# Nuio_Left_Keyboard_Rev_G_Power.net
KiCad netlist of a schematic drawn in Altium Designer
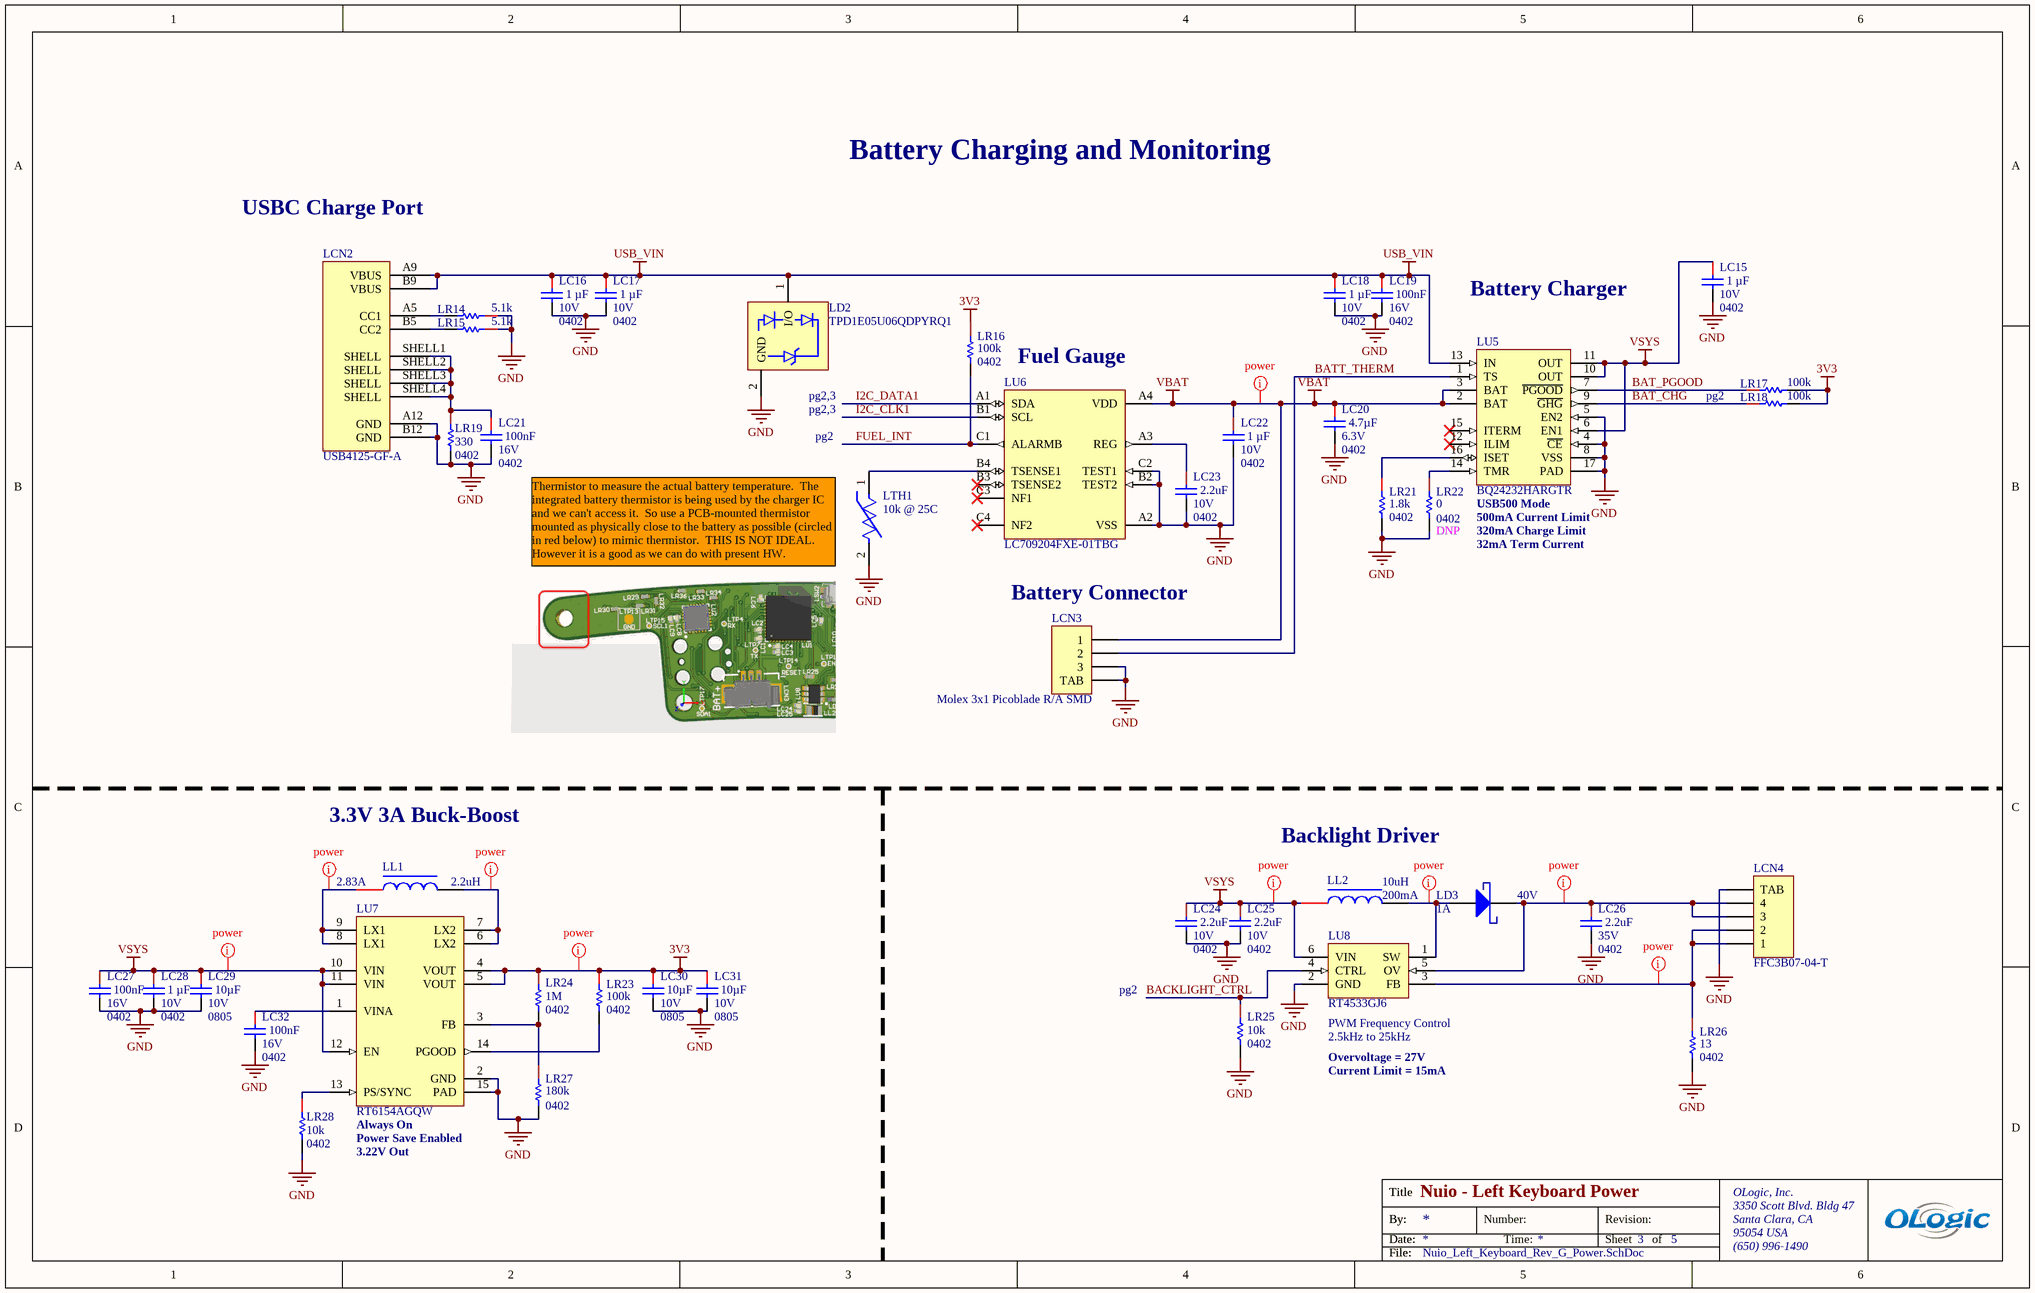
[diagram p0: Nuio_Left_Keyboard_Rev_G_Power.SchDoc]

(export (version "E")
  (design (tool "Eeschema 10.0.6"))
  (components
    (comp (ref "LC15")
      (value "CAP CER 1UF 10V X5R 0402")
      (footprint "CAPC0402(1005)_L")
      (description "±20% 10V Ceramic Capacitor X5R 0402 (1005 Metric)")
      (fields
        (field (name "PACKAGE (IMPERIAL)") "0402")
        (field (name "VOLTAGE (RATED)") "10V")
        (field (name "CAPACITANCE") "1 µF")
        (field (name "MANUFACTURER PART NUMBER") "CC0402MRX5R6BB105")
        (field (name "TOLERANCE") "±20%")
      )
      (libsource (lib "OLogic Nexus Vault") (part "OL_Capacitor"))
    )
    (comp (ref "LC16")
      (value "CAP CER 1UF 10V X5R 0402")
      (footprint "CAPC0402(1005)_L")
      (description "±20% 10V Ceramic Capacitor X5R 0402 (1005 Metric)")
      (fields
        (field (name "PACKAGE (IMPERIAL)") "0402")
        (field (name "VOLTAGE (RATED)") "10V")
        (field (name "CAPACITANCE") "1 µF")
        (field (name "MANUFACTURER PART NUMBER") "CC0402MRX5R6BB105")
        (field (name "TOLERANCE") "±20%")
      )
      (libsource (lib "OLogic Nexus Vault") (part "OL_Capacitor"))
    )
    (comp (ref "LC17")
      (value "CAP CER 1UF 10V X5R 0402")
      (footprint "CAPC0402(1005)_L")
      (description "±20% 10V Ceramic Capacitor X5R 0402 (1005 Metric)")
      (fields
        (field (name "PACKAGE (IMPERIAL)") "0402")
        (field (name "VOLTAGE (RATED)") "10V")
        (field (name "CAPACITANCE") "1 µF")
        (field (name "MANUFACTURER PART NUMBER") "CC0402MRX5R6BB105")
        (field (name "TOLERANCE") "±20%")
      )
      (libsource (lib "OLogic Nexus Vault") (part "OL_Capacitor"))
    )
    (comp (ref "LC18")
      (value "CAP CER 1UF 10V X5R 0402")
      (footprint "CAPC0402(1005)_L")
      (description "±20% 10V Ceramic Capacitor X5R 0402 (1005 Metric)")
      (fields
        (field (name "PACKAGE (IMPERIAL)") "0402")
        (field (name "VOLTAGE (RATED)") "10V")
        (field (name "CAPACITANCE") "1 µF")
        (field (name "MANUFACTURER PART NUMBER") "CC0402MRX5R6BB105")
        (field (name "TOLERANCE") "±20%")
      )
      (libsource (lib "OLogic Nexus Vault") (part "OL_Capacitor"))
    )
    (comp (ref "LC19")
      (value "CAP CER 0.1UF 16V X5R 0402")
      (footprint "CAPC0402(1005)_L")
      (description "±10% 16V Ceramic Capacitor X5R 0402 (1005 Metric)")
      (fields
        (field (name "PACKAGE (IMPERIAL)") "0402")
        (field (name "VOLTAGE (RATED)") "16V")
        (field (name "CAPACITANCE") "100nF")
        (field (name "MANUFACTURER") "Taiyo Yuden")
        (field (name "MANUFACTURER PART NUMBER") "EMK105BJ104KV-F")
      )
      (libsource (lib "OLogic Nexus Vault") (part "OL_Capacitor"))
    )
    (comp (ref "LC20")
      (value "4.7uF")
      (footprint "CAPC0402(1005)_L")
      (description "CAP CER 4.7UF 6.3V 10% X5R 0402")
      (fields
        (field (name "PACKAGE (IMPERIAL)") "0402")
        (field (name "VOLTAGE (RATED)") "6.3V")
        (field (name "CAPACITANCE") "4.7µF")
        (field (name "TOLERANCE") "20%")
      )
      (libsource (lib "OLogic Nexus Vault") (part "OL_Capacitor"))
    )
    (comp (ref "LC21")
      (value "CAP CER 0.1UF 16V X5R 0402")
      (footprint "CAPC0402(1005)_L")
      (description "±10% 16V Ceramic Capacitor X5R 0402 (1005 Metric)")
      (fields
        (field (name "PACKAGE (IMPERIAL)") "0402")
        (field (name "VOLTAGE (RATED)") "16V")
        (field (name "CAPACITANCE") "100nF")
        (field (name "MANUFACTURER") "Taiyo Yuden")
        (field (name "MANUFACTURER PART NUMBER") "EMK105BJ104KV-F")
      )
      (libsource (lib "OLogic Nexus Vault") (part "OL_Capacitor"))
    )
    (comp (ref "LC22")
      (value "CAP CER 1UF 10V X5R 0402")
      (footprint "CAPC0402(1005)_L")
      (description "±20% 10V Ceramic Capacitor X5R 0402 (1005 Metric)")
      (fields
        (field (name "PACKAGE (IMPERIAL)") "0402")
        (field (name "VOLTAGE (RATED)") "10V")
        (field (name "CAPACITANCE") "1 µF")
        (field (name "MANUFACTURER PART NUMBER") "CC0402MRX5R6BB105")
        (field (name "TOLERANCE") "±20%")
      )
      (libsource (lib "OLogic Nexus Vault") (part "OL_Capacitor"))
    )
    (comp (ref "LC23")
      (value "CAP CER 2.2UF 10V X5R 0402")
      (footprint "CAPC0402(1005)_L")
      (description "±20% 10V Ceramic Capacitor X5R 0402 (1005 Metric)")
      (fields
        (field (name "PACKAGE (IMPERIAL)") "0402")
        (field (name "VOLTAGE (RATED)") "10V")
        (field (name "CAPACITANCE") "2.2uF")
        (field (name "TOLERANCE") "20%")
        (field (name "MANUFACTURER") "KEMET")
      )
      (libsource (lib "OLogic Nexus Vault") (part "OL_Capacitor"))
    )
    (comp (ref "LC24")
      (value "CAP CER 2.2UF 10V X5R 0402")
      (footprint "CAPC0402(1005)_L")
      (description "±20% 10V Ceramic Capacitor X5R 0402 (1005 Metric)")
      (fields
        (field (name "PACKAGE (IMPERIAL)") "0402")
        (field (name "VOLTAGE (RATED)") "10V")
        (field (name "CAPACITANCE") "2.2uF")
        (field (name "TOLERANCE") "20%")
        (field (name "MANUFACTURER") "KEMET")
      )
      (libsource (lib "OLogic Nexus Vault") (part "OL_Capacitor"))
    )
    (comp (ref "LC25")
      (value "CAP CER 2.2UF 10V X5R 0402")
      (footprint "CAPC0402(1005)_L")
      (description "±20% 10V Ceramic Capacitor X5R 0402 (1005 Metric)")
      (fields
        (field (name "PACKAGE (IMPERIAL)") "0402")
        (field (name "VOLTAGE (RATED)") "10V")
        (field (name "CAPACITANCE") "2.2uF")
        (field (name "TOLERANCE") "20%")
        (field (name "MANUFACTURER") "KEMET")
      )
      (libsource (lib "OLogic Nexus Vault") (part "OL_Capacitor"))
    )
    (comp (ref "LC26")
      (value "2.2uF")
      (footprint "CAPC0402(1005)_L")
      (description "CAP CER 2.2UF 35V 10% X5R 0402")
      (fields
        (field (name "VOLTAGE (RATED)") "35V")
        (field (name "PACKAGE (IMPERIAL)") "0402")
        (field (name "TOLERANCE") "10%")
      )
      (libsource (lib "OLogic Nexus Vault") (part "=Capacitance"))
    )
    (comp (ref "LC27")
      (value "CAP CER 0.1UF 16V X5R 0402")
      (footprint "CAPC0402(1005)_L")
      (description "±10% 16V Ceramic Capacitor X5R 0402 (1005 Metric)")
      (fields
        (field (name "PACKAGE (IMPERIAL)") "0402")
        (field (name "VOLTAGE (RATED)") "16V")
        (field (name "CAPACITANCE") "100nF")
        (field (name "MANUFACTURER") "Taiyo Yuden")
        (field (name "MANUFACTURER PART NUMBER") "EMK105BJ104KV-F")
      )
      (libsource (lib "OLogic Nexus Vault") (part "OL_Capacitor"))
    )
    (comp (ref "LC28")
      (value "CAP CER 1UF 10V X5R 0402")
      (footprint "CAPC0402(1005)_L")
      (description "±20% 10V Ceramic Capacitor X5R 0402 (1005 Metric)")
      (fields
        (field (name "PACKAGE (IMPERIAL)") "0402")
        (field (name "VOLTAGE (RATED)") "10V")
        (field (name "CAPACITANCE") "1 µF")
        (field (name "MANUFACTURER PART NUMBER") "CC0402MRX5R6BB105")
        (field (name "TOLERANCE") "±20%")
      )
      (libsource (lib "OLogic Nexus Vault") (part "OL_Capacitor"))
    )
    (comp (ref "LC29")
      (value "CAP CER 10UF 10V X7R 0805")
      (footprint "CAPC0805(2012)_L")
      (description "10µF ±10% 10V Ceramic Capacitor X7R 0805 (2012 Metric)")
      (fields
        (field (name "VOLTAGE (RATED)") "10V")
        (field (name "PACKAGE (IMPERIAL)") "0805")
        (field (name "CAPACITANCE") "10µF")
        (field (name "TOLERANCE") "10%")
        (field (name "MANUFACTURER PART NUMBER") "GRM21BR71A106KA73K")
      )
      (libsource (lib "OLogic Nexus Vault") (part "OL_Capacitor"))
    )
    (comp (ref "LC30")
      (value "CAP CER 10UF 10V X7R 0805")
      (footprint "CAPC0805(2012)_L")
      (description "10µF ±10% 10V Ceramic Capacitor X7R 0805 (2012 Metric)")
      (fields
        (field (name "VOLTAGE (RATED)") "10V")
        (field (name "PACKAGE (IMPERIAL)") "0805")
        (field (name "CAPACITANCE") "10µF")
        (field (name "TOLERANCE") "10%")
        (field (name "MANUFACTURER PART NUMBER") "GRM21BR71A106KA73K")
      )
      (libsource (lib "OLogic Nexus Vault") (part "OL_Capacitor"))
    )
    (comp (ref "LC31")
      (value "CAP CER 10UF 10V X7R 0805")
      (footprint "CAPC0805(2012)_L")
      (description "10µF ±10% 10V Ceramic Capacitor X7R 0805 (2012 Metric)")
      (fields
        (field (name "VOLTAGE (RATED)") "10V")
        (field (name "PACKAGE (IMPERIAL)") "0805")
        (field (name "CAPACITANCE") "10µF")
        (field (name "TOLERANCE") "10%")
        (field (name "MANUFACTURER PART NUMBER") "GRM21BR71A106KA73K")
      )
      (libsource (lib "OLogic Nexus Vault") (part "OL_Capacitor"))
    )
    (comp (ref "LC32")
      (value "CAP CER 0.1UF 16V X5R 0402")
      (footprint "CAPC0402(1005)_L")
      (description "±10% 16V Ceramic Capacitor X5R 0402 (1005 Metric)")
      (fields
        (field (name "PACKAGE (IMPERIAL)") "0402")
        (field (name "VOLTAGE (RATED)") "16V")
        (field (name "CAPACITANCE") "100nF")
        (field (name "MANUFACTURER") "Taiyo Yuden")
        (field (name "MANUFACTURER PART NUMBER") "EMK105BJ104KV-F")
      )
      (libsource (lib "OLogic Nexus Vault") (part "OL_Capacitor"))
    )
    (comp (ref "LCN2")
      (value "USB4125-GF-A")
      (footprint "USB4125-GF-A")
      (fields (field (name "MANUFACTURER") "GCT") (field (name "VOLTAGE") "20V"))
      (libsource (lib "OLogic Nexus Vault") (part "USB4125-GF-A"))
    )
    (comp (ref "LCN3")
      (value "Molex 3x1 Picoblade R/A SMD")
      (footprint "Molex 3x1 Picoblade R_A SMD")
      (description "1.25mm (.049\") Pitch PicoBlade Header, Surface Mount, Right Angle, Lead-free, 3 Circuits")
      (libsource (lib "Nuio_Left_Keyboard_Rev_G") (part "CMP-00344-01"))
    )
    (comp (ref "LCN4")
      (value "FFC3B07-04-T")
      (footprint "FFC3B07-04-T")
      (fields (field (name "MANUFACTURER") "GCT"))
      (libsource (lib "OLogic Nexus Vault") (part "FFC3B07-04-T"))
    )
    (comp (ref "LD2")
      (value "TPD1E05U06QDPYRQ1")
      (footprint "FP-DPY0002A-MFG")
      (description "TVS DIODE 5.5V 14V 2X1SON")
      (fields (field (name "MANUFACTURER") "Texas Instruments"))
      (libsource (lib "OLogic Nexus Vault") (part "TPD1E05U06QDPYRQ1"))
    )
    (comp (ref "LD3")
      (value "PMEG4010AESBYL")
      (footprint "PMEG4010AESBYL-Footprint-1")
      (description "DIODE SCHOTTKY 40V 1A SOD993")
      (fields (field (name "DC REVERSE VOLTAGE MAX") "40V") (field (name "CURRENT AVG RECTIFIED") "1A"))
      (libsource (lib "OLogic Nexus Vault") (part "PMEG4010AESB"))
    )
    (comp (ref "LL1")
      (value "FIXED IND 2.2UH 2.83A 74MOHM SMD")
      (footprint "FIXED IND 2.2UH 2.83A 74MOHM SMD")
      (description "2.2 µH Shielded Wirewound Inductor 2.83 A 74mOhm Max Nonstandard -")
      (fields
        (field (name "INDUCTANCE") "2.2uH")
        (field (name "CURRENT RATING (AMPS)") "2.83A")
        (field (name "MANUFACTURER") "TDK Corporation")
      )
      (libsource (lib "OLogic Nexus Vault") (part "OL_Inductor"))
    )
    (comp (ref "LL2")
      (value "10uH")
      (footprint "FIXED IND 10UH 300MA 680MOHM SMD")
      (description "10 µH Shielded Multilayer Inductor 300 mA 680mOhm 0805 (2012 Metric)")
      (fields
        (field (name "MANUFACTURER PART NUMBER") "MLZ2012M100HT000")
        (field (name "TOLERANCE") "20%")
        (field (name "SATURATION CURRENT") "200mA")
      )
      (libsource (lib "OLogic Nexus Vault") (part "OL_Inductor"))
    )
    (comp (ref "LR14")
      (value "RES SMD 5.1K OHM 1% 1/10W 0402")
      (footprint "RESC0402(1005)_L")
      (description "5.1 kOhms ±1% 0.1W, 1/10W Chip Resistor 0402 (1005 Metric) Automotive AEC-Q200 Thick Film")
      (fields
        (field (name "RESISTANCE") "5.1k")
        (field (name "POWER") "63mW")
        (field (name "TOLERANCE") "1%")
      )
      (libsource (lib "OLogic Nexus Vault") (part "=Resistance"))
    )
    (comp (ref "LR15")
      (value "RES SMD 5.1K OHM 1% 1/10W 0402")
      (footprint "RESC0402(1005)_L")
      (description "5.1 kOhms ±1% 0.1W, 1/10W Chip Resistor 0402 (1005 Metric) Automotive AEC-Q200 Thick Film")
      (fields
        (field (name "RESISTANCE") "5.1k")
        (field (name "POWER") "63mW")
        (field (name "TOLERANCE") "1%")
      )
      (libsource (lib "OLogic Nexus Vault") (part "=Resistance"))
    )
    (comp (ref "LR16")
      (value "100k")
      (footprint "RESC0402(1005)_L")
      (description "±1% 0.063W, 1/16W Chip Resistor 0402 (1005 Metric) Moisture Resistant Thick Film")
      (fields
        (field (name "CASE CODE (IMPERIAL)") "0402")
        (field (name "TOLERANCE") "1%")
        (field (name "MANUFACTURER") "YAGEO")
      )
      (libsource (lib "OLogic Nexus Vault") (part "=Resistance"))
    )
    (comp (ref "LR17")
      (value "100k")
      (footprint "RESC0402(1005)_L")
      (description "±1% 0.063W, 1/16W Chip Resistor 0402 (1005 Metric) Moisture Resistant Thick Film")
      (fields (field (name "TOLERANCE") "1%") (field (name "MANUFACTURER") "YAGEO"))
      (libsource (lib "OLogic Nexus Vault") (part "=Resistance"))
    )
    (comp (ref "LR18")
      (value "100k")
      (footprint "RESC0402(1005)_L")
      (description "±1% 0.063W, 1/16W Chip Resistor 0402 (1005 Metric) Moisture Resistant Thick Film")
      (fields (field (name "TOLERANCE") "1%") (field (name "MANUFACTURER") "YAGEO"))
      (libsource (lib "OLogic Nexus Vault") (part "=Resistance"))
    )
    (comp (ref "LR19")
      (value "RES SMD 330 OHM 1% 1/16W 0402")
      (footprint "RESC0402(1005)_L")
      (description "330 Ohms ±1% 0.063W, 1/16W Chip Resistor 0402 (1005 Metric) Automotive AEC-Q200 Thick Film")
      (fields
        (field (name "RESISTANCE") "330")
        (field (name "PACKAGE (IMPERIAL)") "0402")
        (field (name "POWER") "63mW")
        (field (name "TOLERANCE") "1%")
      )
      (libsource (lib "OLogic Nexus Vault") (part "OL_Resistor"))
    )
    (comp (ref "LR21")
      (value "1.8k")
      (footprint "RESC0402(1005)_L")
      (description "1.8 kOhms ±0.1% 0.063W, 1/16W Chip Resistor 0402 (1005 Metric) Automotive AEC-Q200 Thin Film")
      (fields
        (field (name "TOLERANCE") "0.1%")
        (field (name "CASE CODE (IMPERIAL)") "0402")
        (field (name "MANUFACTURER") "Panasonic Electronic Components")
      )
      (libsource (lib "OLogic Nexus Vault") (part "=Resistance"))
    )
    (comp (ref "LR22")
      (value "RES 0 OHM JUMPER 1/16W 0402")
      (footprint "RESC0402(1005)_L")
      (description "0 Ohms Jumper Chip Resistor 0402 (1005 Metric) Automotive AEC-Q200 Thick Film")
      (fields
        (field (name "PACKAGE (IMPERIAL)") "0402")
        (field (name "RESISTANCE") "0")
        (field (name "POWER") "63mW")
        (field (name "TOLERANCE") "0%")
      )
      (libsource (lib "OLogic Nexus Vault") (part "=Resistance"))
    )
    (comp (ref "LR23")
      (value "100k")
      (footprint "RESC0402(1005)_L")
      (description "±1% 0.063W, 1/16W Chip Resistor 0402 (1005 Metric) Moisture Resistant Thick Film")
      (fields
        (field (name "CASE CODE (IMPERIAL)") "0402")
        (field (name "TOLERANCE") "1%")
        (field (name "MANUFACTURER") "YAGEO")
      )
      (libsource (lib "OLogic Nexus Vault") (part "=Resistance"))
    )
    (comp (ref "LR24")
      (value "RES 1M OHM 1% 1/16W 0402")
      (footprint "RESC0402(1005)_L")
      (description "1 MOhms ±1% 0.063W, 1/16W Chip Resistor 0402 (1005 Metric) Moisture Resistant Thick Film")
      (fields
        (field (name "RESISTANCE") "1M")
        (field (name "CASE/PACKAGE") "0402")
        (field (name "MANUFACTURER") "YAGEO")
        (field (name "MANUFACTURER PART NUMBER") "RC0402FR-071ML")
      )
      (libsource (lib "OLogic Nexus Vault") (part "OL_Resistor"))
    )
    (comp (ref "LR25")
      (value "RES SMD 10K OHM 1% 1/16W 0402")
      (footprint "RESC0402_YAGEO")
      (fields
        (field (name "RESISTANCE") "10k")
        (field (name "PACKAGE (IMPERIAL)") "0402")
        (field (name "MANUFACTURER") "Yageo")
        (field (name "TOLERANCE") "1%")
        (field (name "MANUFACTURER PART NUMBER") "AT0402FRE0710KL")
      )
      (libsource (lib "OLogic Nexus Vault") (part "OL_Resistor"))
    )
    (comp (ref "LR26")
      (value "13")
      (footprint "RESC0402(1005)_L")
      (description "SMD Chip Resistor, 13 Ohm, ± 1%, 63 mW, 0402 [1005 Metric], Thick Film, General Purpose")
      (fields (field (name "TOLERANCE") "1%") (field (name "CASE/PACKAGE") "0402"))
      (libsource (lib "Nuio_Left_Keyboard_Rev_G") (part "CMP-001-2304-01"))
    )
    (comp (ref "LR27")
      (value "180k")
      (footprint "RESC0402(1005)_L")
      (description "RES 180K OHM 1% 1/16W 0402")
      (fields
        (field (name "PACKAGE (IMPERIAL)") "0402")
        (field (name "POWER") "63mW")
        (field (name "TOLERANCE") "1%")
        (field (name "RESISTANCE") "180k")
      )
      (libsource (lib "OLogic Nexus Vault") (part "=Resistance"))
    )
    (comp (ref "LR28")
      (value "RES SMD 10K OHM 1% 1/16W 0402")
      (footprint "RESC0402_YAGEO")
      (fields
        (field (name "RESISTANCE") "10k")
        (field (name "PACKAGE (IMPERIAL)") "0402")
        (field (name "MANUFACTURER") "Yageo")
        (field (name "TOLERANCE") "1%")
        (field (name "MANUFACTURER PART NUMBER") "AT0402FRE0710KL")
      )
      (libsource (lib "OLogic Nexus Vault") (part "OL_Resistor"))
    )
    (comp (ref "LTH1")
      (value "10k @ 25C")
      (footprint "FP-NCP15-NCU15-0_05-IPC_A")
      (description "NTC Thermistor for Temperature Sensor, Automotive, 0402, 10kΩ, 1%, 0.1mA, 5V")
      (libsource (lib "Altium Content Vault") (part "3b148a6ebabc5fb4d708a66c052d352"))
    )
    (comp (ref "LU5")
      (value "BQ24232HARGTR")
      (footprint "BQ24232HARGTR")
      (description "USB Friendly 0.5A Li-ion charger with power-Path, 10.5V OVP 16-VQFN -5 to 125")
      (libsource (lib "Nuio_Left_Keyboard_Rev_G") (part "CMP-001-1983-03"))
    )
    (comp (ref "LU6")
      (value "LC709204FXE-01TBG")
      (footprint "BGA12C40P4X3_191X148X51")
      (description "IC FUEL GAUGE LI-ION 1C 12WLCSP")
      (fields (field (name "MANUFACTURER") "onsemi"))
      (libsource (lib "OLogic Nexus Vault") (part "LC709204FXE-01TBG"))
    )
    (comp (ref "LU7")
      (value "RT6154AGQW")
      (footprint "PSON50P300X80_HS-15N")
      (description "IC REG BCK BST ADJ 4A 14WDFN")
      (fields (field (name "MANUFACTURER") "Richtek USA Inc."))
      (libsource (lib "OLogic Nexus Vault") (part "RT6154AGQW"))
    )
    (comp (ref "LU8")
      (value "RT4533GJ6")
      (footprint "RT4533GJ6")
      (description "IC LED DRVR RGLTR PWM TSOT23-6")
      (libsource (lib "OLogic Nexus Vault") (part "RT4533GJ6"))
    )
  )
  (nets
    (net (code "1") (name "/BACKLIGHT_CTRL") (class "Default")
      (node (ref "LR25") (pin "1") (pinfunction "1_1") (pintype "passive"))
      (node (ref "LU8") (pin "4") (pinfunction "CTRL_4") (pintype "input"))
    )
    (net (code "2") (name "/BATT_THERM") (class "Default")
      (node (ref "LCN3") (pin "2") (pinfunction "2_2") (pintype "passive"))
      (node (ref "LU5") (pin "1") (pinfunction "TS_1") (pintype "input"))
    )
    (net (code "3") (name "/BAT_CHG") (class "Default")
      (node (ref "LR18") (pin "1") (pinfunction "1_1") (pintype "passive"))
      (node (ref "LU5") (pin "9") (pinfunction "~{GHG}_9") (pintype "output"))
    )
    (net (code "4") (name "/BAT_PGOOD") (class "Default")
      (node (ref "LR17") (pin "1") (pinfunction "1_1") (pintype "passive"))
      (node (ref "LU5") (pin "7") (pinfunction "~{PGOOD}_7") (pintype "output"))
    )
    (net (code "5") (name "/FUEL_INT") (class "Default")
      (node (ref "LR16") (pin "2") (pinfunction "2_2") (pintype "passive"))
      (node (ref "LU6") (pin "C1") (pinfunction "ALARMB_C1") (pintype "output"))
    )
    (net (code "6") (name "/I2C_CLK1") (class "Default")
      (node (ref "LU6") (pin "B1") (pinfunction "SCL_B1") (pintype "bidirectional"))
    )
    (net (code "7") (name "/I2C_DATA1") (class "Default")
      (node (ref "LU6") (pin "A1") (pinfunction "SDA_A1") (pintype "bidirectional"))
    )
    (net (code "8") (name "3V3") (class "Default")
      (node (ref "LC30") (pin "1") (pinfunction "1_1") (pintype "passive"))
      (node (ref "LC31") (pin "1") (pinfunction "1_1") (pintype "passive"))
      (node (ref "LR16") (pin "1") (pinfunction "1_1") (pintype "passive"))
      (node (ref "LR17") (pin "2") (pinfunction "2_2") (pintype "passive"))
      (node (ref "LR18") (pin "2") (pinfunction "2_2") (pintype "passive"))
      (node (ref "LR23") (pin "1") (pinfunction "1_1") (pintype "passive"))
      (node (ref "LR24") (pin "1") (pinfunction "1_1") (pintype "passive"))
      (node (ref "LU7") (pin "4") (pinfunction "VOUT_4") (pintype "power_in"))
      (node (ref "LU7") (pin "5") (pinfunction "VOUT_5") (pintype "power_in"))
    )
    (net (code "9") (name "GND") (class "Default")
      (node (ref "LC15") (pin "2") (pinfunction "2_2") (pintype "passive"))
      (node (ref "LC16") (pin "2") (pinfunction "2_2") (pintype "passive"))
      (node (ref "LC17") (pin "2") (pinfunction "2_2") (pintype "passive"))
      (node (ref "LC18") (pin "2") (pinfunction "2_2") (pintype "passive"))
      (node (ref "LC19") (pin "2") (pinfunction "2_2") (pintype "passive"))
      (node (ref "LC20") (pin "2") (pinfunction "2_2") (pintype "passive"))
      (node (ref "LC21") (pin "2") (pinfunction "2_2") (pintype "passive"))
      (node (ref "LC22") (pin "2") (pinfunction "2_2") (pintype "passive"))
      (node (ref "LC23") (pin "2") (pinfunction "2_2") (pintype "passive"))
      (node (ref "LC24") (pin "2") (pinfunction "2_2") (pintype "passive"))
      (node (ref "LC25") (pin "2") (pinfunction "2_2") (pintype "passive"))
      (node (ref "LC26") (pin "2") (pinfunction "2_2") (pintype "passive"))
      (node (ref "LC27") (pin "2") (pinfunction "2_2") (pintype "passive"))
      (node (ref "LC28") (pin "2") (pinfunction "2_2") (pintype "passive"))
      (node (ref "LC29") (pin "2") (pinfunction "2_2") (pintype "passive"))
      (node (ref "LC30") (pin "2") (pinfunction "2_2") (pintype "passive"))
      (node (ref "LC31") (pin "2") (pinfunction "2_2") (pintype "passive"))
      (node (ref "LC32") (pin "2") (pinfunction "2_2") (pintype "passive"))
      (node (ref "LCN2") (pin "A12") (pinfunction "GND_A12") (pintype "passive"))
      (node (ref "LCN2") (pin "B12") (pinfunction "GND_B12") (pintype "passive"))
      (node (ref "LCN3") (pin "0") (pinfunction "TAB_0") (pintype "passive"))
      (node (ref "LCN3") (pin "3") (pinfunction "3_3") (pintype "passive"))
      (node (ref "LCN4") (pin "0") (pinfunction "TAB_0") (pintype "passive"))
      (node (ref "LD2") (pin "2") (pinfunction "GND_2") (pintype "passive"))
      (node (ref "LR14") (pin "1") (pinfunction "1_1") (pintype "passive"))
      (node (ref "LR15") (pin "1") (pinfunction "1_1") (pintype "passive"))
      (node (ref "LR19") (pin "2") (pinfunction "2_2") (pintype "passive"))
      (node (ref "LR21") (pin "2") (pinfunction "2_2") (pintype "passive"))
      (node (ref "LR22") (pin "2") (pinfunction "2_2") (pintype "passive"))
      (node (ref "LR25") (pin "2") (pinfunction "2_2") (pintype "passive"))
      (node (ref "LR26") (pin "2") (pinfunction "2_2") (pintype "passive"))
      (node (ref "LR27") (pin "2") (pinfunction "2_2") (pintype "passive"))
      (node (ref "LR28") (pin "2") (pinfunction "2_2") (pintype "passive"))
      (node (ref "LTH1") (pin "2") (pinfunction "2_2") (pintype "passive"))
      (node (ref "LU5") (pin "17") (pinfunction "PAD_17") (pintype "passive"))
      (node (ref "LU5") (pin "4") (pinfunction "~{CE}_4") (pintype "input"))
      (node (ref "LU5") (pin "5") (pinfunction "EN2_5") (pintype "input"))
      (node (ref "LU5") (pin "8") (pinfunction "VSS_8") (pintype "passive"))
      (node (ref "LU6") (pin "A2") (pinfunction "VSS_A2") (pintype "power_in"))
      (node (ref "LU6") (pin "B2") (pinfunction "TEST2_B2") (pintype "input"))
      (node (ref "LU6") (pin "C2") (pinfunction "TEST1_C2") (pintype "input"))
      (node (ref "LU7") (pin "15") (pinfunction "PAD_15") (pintype "power_in"))
      (node (ref "LU7") (pin "2") (pinfunction "GND_2") (pintype "power_in"))
      (node (ref "LU8") (pin "2") (pinfunction "GND_2") (pintype "power_in"))
    )
    (net (code "10") (name "Net-(LC21-Pad1)") (class "Default")
      (node (ref "LC21") (pin "1") (pinfunction "1_1") (pintype "passive"))
      (node (ref "LCN2") (pin "SHELL1") (pinfunction "SHELL_SHELL1") (pintype "passive"))
      (node (ref "LCN2") (pin "SHELL2") (pinfunction "SHELL_SHELL2") (pintype "passive"))
      (node (ref "LCN2") (pin "SHELL3") (pinfunction "SHELL_SHELL3") (pintype "passive"))
      (node (ref "LCN2") (pin "SHELL4") (pinfunction "SHELL_SHELL4") (pintype "passive"))
      (node (ref "LR19") (pin "1") (pinfunction "1_1") (pintype "passive"))
    )
    (net (code "11") (name "Net-(LCN2-CC1)") (class "Default")
      (node (ref "LCN2") (pin "A5") (pinfunction "CC1_A5") (pintype "passive"))
      (node (ref "LR14") (pin "2") (pinfunction "2_2") (pintype "passive"))
    )
    (net (code "12") (name "Net-(LCN2-CC2)") (class "Default")
      (node (ref "LCN2") (pin "B5") (pinfunction "CC2_B5") (pintype "passive"))
      (node (ref "LR15") (pin "2") (pinfunction "2_2") (pintype "passive"))
    )
    (net (code "13") (name "Net-(LD3-A)") (class "Default")
      (node (ref "LD3") (pin "2") (pinfunction "A_2") (pintype "passive"))
      (node (ref "LL2") (pin "2") (pinfunction "2_2") (pintype "passive"))
      (node (ref "LU8") (pin "1") (pinfunction "SW_1") (pintype "passive"))
    )
    (net (code "14") (name "Net-(LD3-K)") (class "Default")
      (node (ref "LC26") (pin "1") (pinfunction "1_1") (pintype "passive"))
      (node (ref "LCN4") (pin "3") (pinfunction "3_3") (pintype "passive"))
      (node (ref "LCN4") (pin "4") (pinfunction "4_4") (pintype "passive"))
      (node (ref "LD3") (pin "1") (pinfunction "K_1") (pintype "passive"))
      (node (ref "LU8") (pin "5") (pinfunction "OV_5") (pintype "input"))
    )
    (net (code "15") (name "Net-(LL1-Pad1)") (class "Default")
      (node (ref "LL1") (pin "1") (pinfunction "1_1") (pintype "passive"))
      (node (ref "LU7") (pin "8") (pinfunction "LX1_8") (pintype "passive"))
      (node (ref "LU7") (pin "9") (pinfunction "LX1_9") (pintype "passive"))
    )
    (net (code "16") (name "Net-(LL1-Pad2)") (class "Default")
      (node (ref "LL1") (pin "2") (pinfunction "2_2") (pintype "passive"))
      (node (ref "LU7") (pin "6") (pinfunction "LX2_6") (pintype "passive"))
      (node (ref "LU7") (pin "7") (pinfunction "LX2_7") (pintype "passive"))
    )
    (net (code "17") (name "Net-(LU5-ISET)") (class "Default")
      (node (ref "LR21") (pin "1") (pinfunction "1_1") (pintype "passive"))
      (node (ref "LU5") (pin "16") (pinfunction "ISET_16") (pintype "bidirectional"))
    )
    (net (code "18") (name "Net-(LU5-TMR)") (class "Default")
      (node (ref "LR22") (pin "1") (pinfunction "1_1") (pintype "passive"))
      (node (ref "LU5") (pin "14") (pinfunction "TMR_14") (pintype "input"))
    )
    (net (code "19") (name "Net-(LU6-REG)") (class "Default")
      (node (ref "LC23") (pin "1") (pinfunction "1_1") (pintype "passive"))
      (node (ref "LU6") (pin "A3") (pinfunction "REG_A3") (pintype "output"))
    )
    (net (code "20") (name "Net-(LU6-TSENSE1)") (class "Default")
      (node (ref "LTH1") (pin "1") (pinfunction "1_1") (pintype "passive"))
      (node (ref "LU6") (pin "B4") (pinfunction "TSENSE1_B4") (pintype "bidirectional"))
    )
    (net (code "21") (name "Net-(LU7-FB)") (class "Default")
      (node (ref "LR24") (pin "2") (pinfunction "2_2") (pintype "passive"))
      (node (ref "LR27") (pin "1") (pinfunction "1_1") (pintype "passive"))
      (node (ref "LU7") (pin "3") (pinfunction "FB_3") (pintype "passive"))
    )
    (net (code "22") (name "Net-(LU7-PGOOD)") (class "Default")
      (node (ref "LR23") (pin "2") (pinfunction "2_2") (pintype "passive"))
      (node (ref "LU7") (pin "14") (pinfunction "PGOOD_14") (pintype "output"))
    )
    (net (code "23") (name "Net-(LU7-PS{slash}SYNC)") (class "Default")
      (node (ref "LR28") (pin "1") (pinfunction "1_1") (pintype "passive"))
      (node (ref "LU7") (pin "13") (pinfunction "PS/SYNC_13") (pintype "input"))
    )
    (net (code "24") (name "Net-(LU7-VINA)") (class "Default")
      (node (ref "LC32") (pin "1") (pinfunction "1_1") (pintype "passive"))
      (node (ref "LU7") (pin "1") (pinfunction "VINA_1") (pintype "power_in"))
    )
    (net (code "25") (name "Net-(LU8-FB)") (class "Default")
      (node (ref "LCN4") (pin "1") (pinfunction "1_1") (pintype "passive"))
      (node (ref "LCN4") (pin "2") (pinfunction "2_2") (pintype "passive"))
      (node (ref "LR26") (pin "1") (pinfunction "1_1") (pintype "passive"))
      (node (ref "LU8") (pin "3") (pinfunction "FB_3") (pintype "passive"))
    )
    (net (code "26") (name "USB_VIN") (class "Default")
      (node (ref "LC16") (pin "1") (pinfunction "1_1") (pintype "passive"))
      (node (ref "LC17") (pin "1") (pinfunction "1_1") (pintype "passive"))
      (node (ref "LC18") (pin "1") (pinfunction "1_1") (pintype "passive"))
      (node (ref "LC19") (pin "1") (pinfunction "1_1") (pintype "passive"))
      (node (ref "LCN2") (pin "A9") (pinfunction "VBUS_A9") (pintype "passive"))
      (node (ref "LCN2") (pin "B9") (pinfunction "VBUS_B9") (pintype "passive"))
      (node (ref "LD2") (pin "1") (pinfunction "I/O_1") (pintype "passive"))
      (node (ref "LU5") (pin "13") (pinfunction "IN_13") (pintype "input"))
    )
    (net (code "27") (name "VBAT") (class "Default")
      (node (ref "LC20") (pin "1") (pinfunction "1_1") (pintype "passive"))
      (node (ref "LC22") (pin "1") (pinfunction "1_1") (pintype "passive"))
      (node (ref "LCN3") (pin "1") (pinfunction "1_1") (pintype "passive"))
      (node (ref "LU5") (pin "2") (pinfunction "BAT_2") (pintype "passive"))
      (node (ref "LU5") (pin "3") (pinfunction "BAT_3") (pintype "passive"))
      (node (ref "LU6") (pin "A4") (pinfunction "VDD_A4") (pintype "power_in"))
    )
    (net (code "28") (name "VSYS") (class "Default")
      (node (ref "LC15") (pin "1") (pinfunction "1_1") (pintype "passive"))
      (node (ref "LC24") (pin "1") (pinfunction "1_1") (pintype "passive"))
      (node (ref "LC25") (pin "1") (pinfunction "1_1") (pintype "passive"))
      (node (ref "LC27") (pin "1") (pinfunction "1_1") (pintype "passive"))
      (node (ref "LC28") (pin "1") (pinfunction "1_1") (pintype "passive"))
      (node (ref "LC29") (pin "1") (pinfunction "1_1") (pintype "passive"))
      (node (ref "LL2") (pin "1") (pinfunction "1_1") (pintype "passive"))
      (node (ref "LU5") (pin "10") (pinfunction "OUT_10") (pintype "passive"))
      (node (ref "LU5") (pin "11") (pinfunction "OUT_11") (pintype "passive"))
      (node (ref "LU5") (pin "6") (pinfunction "EN1_6") (pintype "input"))
      (node (ref "LU7") (pin "10") (pinfunction "VIN_10") (pintype "power_in"))
      (node (ref "LU7") (pin "11") (pinfunction "VIN_11") (pintype "power_in"))
      (node (ref "LU7") (pin "12") (pinfunction "EN_12") (pintype "input"))
      (node (ref "LU8") (pin "6") (pinfunction "VIN_6") (pintype "power_in"))
    )
    (net (code "29") (name "unconnected-(LU5-ILIM-Pad12)") (class "Default")
      (node (ref "LU5") (pin "12") (pinfunction "ILIM_12") (pintype "input+no_connect"))
    )
    (net (code "30") (name "unconnected-(LU5-ITERM-Pad15)") (class "Default")
      (node (ref "LU5") (pin "15") (pinfunction "ITERM_15") (pintype "input+no_connect"))
    )
    (net (code "31") (name "unconnected-(LU6-NF1-PadC3)") (class "Default")
      (node (ref "LU6") (pin "C3") (pinfunction "NF1_C3") (pintype "passive+no_connect"))
    )
    (net (code "32") (name "unconnected-(LU6-NF2-PadC4)") (class "Default")
      (node (ref "LU6") (pin "C4") (pinfunction "NF2_C4") (pintype "passive+no_connect"))
    )
    (net (code "33") (name "unconnected-(LU6-TSENSE2-PadB3)") (class "Default")
      (node (ref "LU6") (pin "B3") (pinfunction "TSENSE2_B3") (pintype "bidirectional+no_connect"))
    )
  )
)
